# Analogica_HB_preto.net
KiCad netlist of a schematic drawn in EAGLE
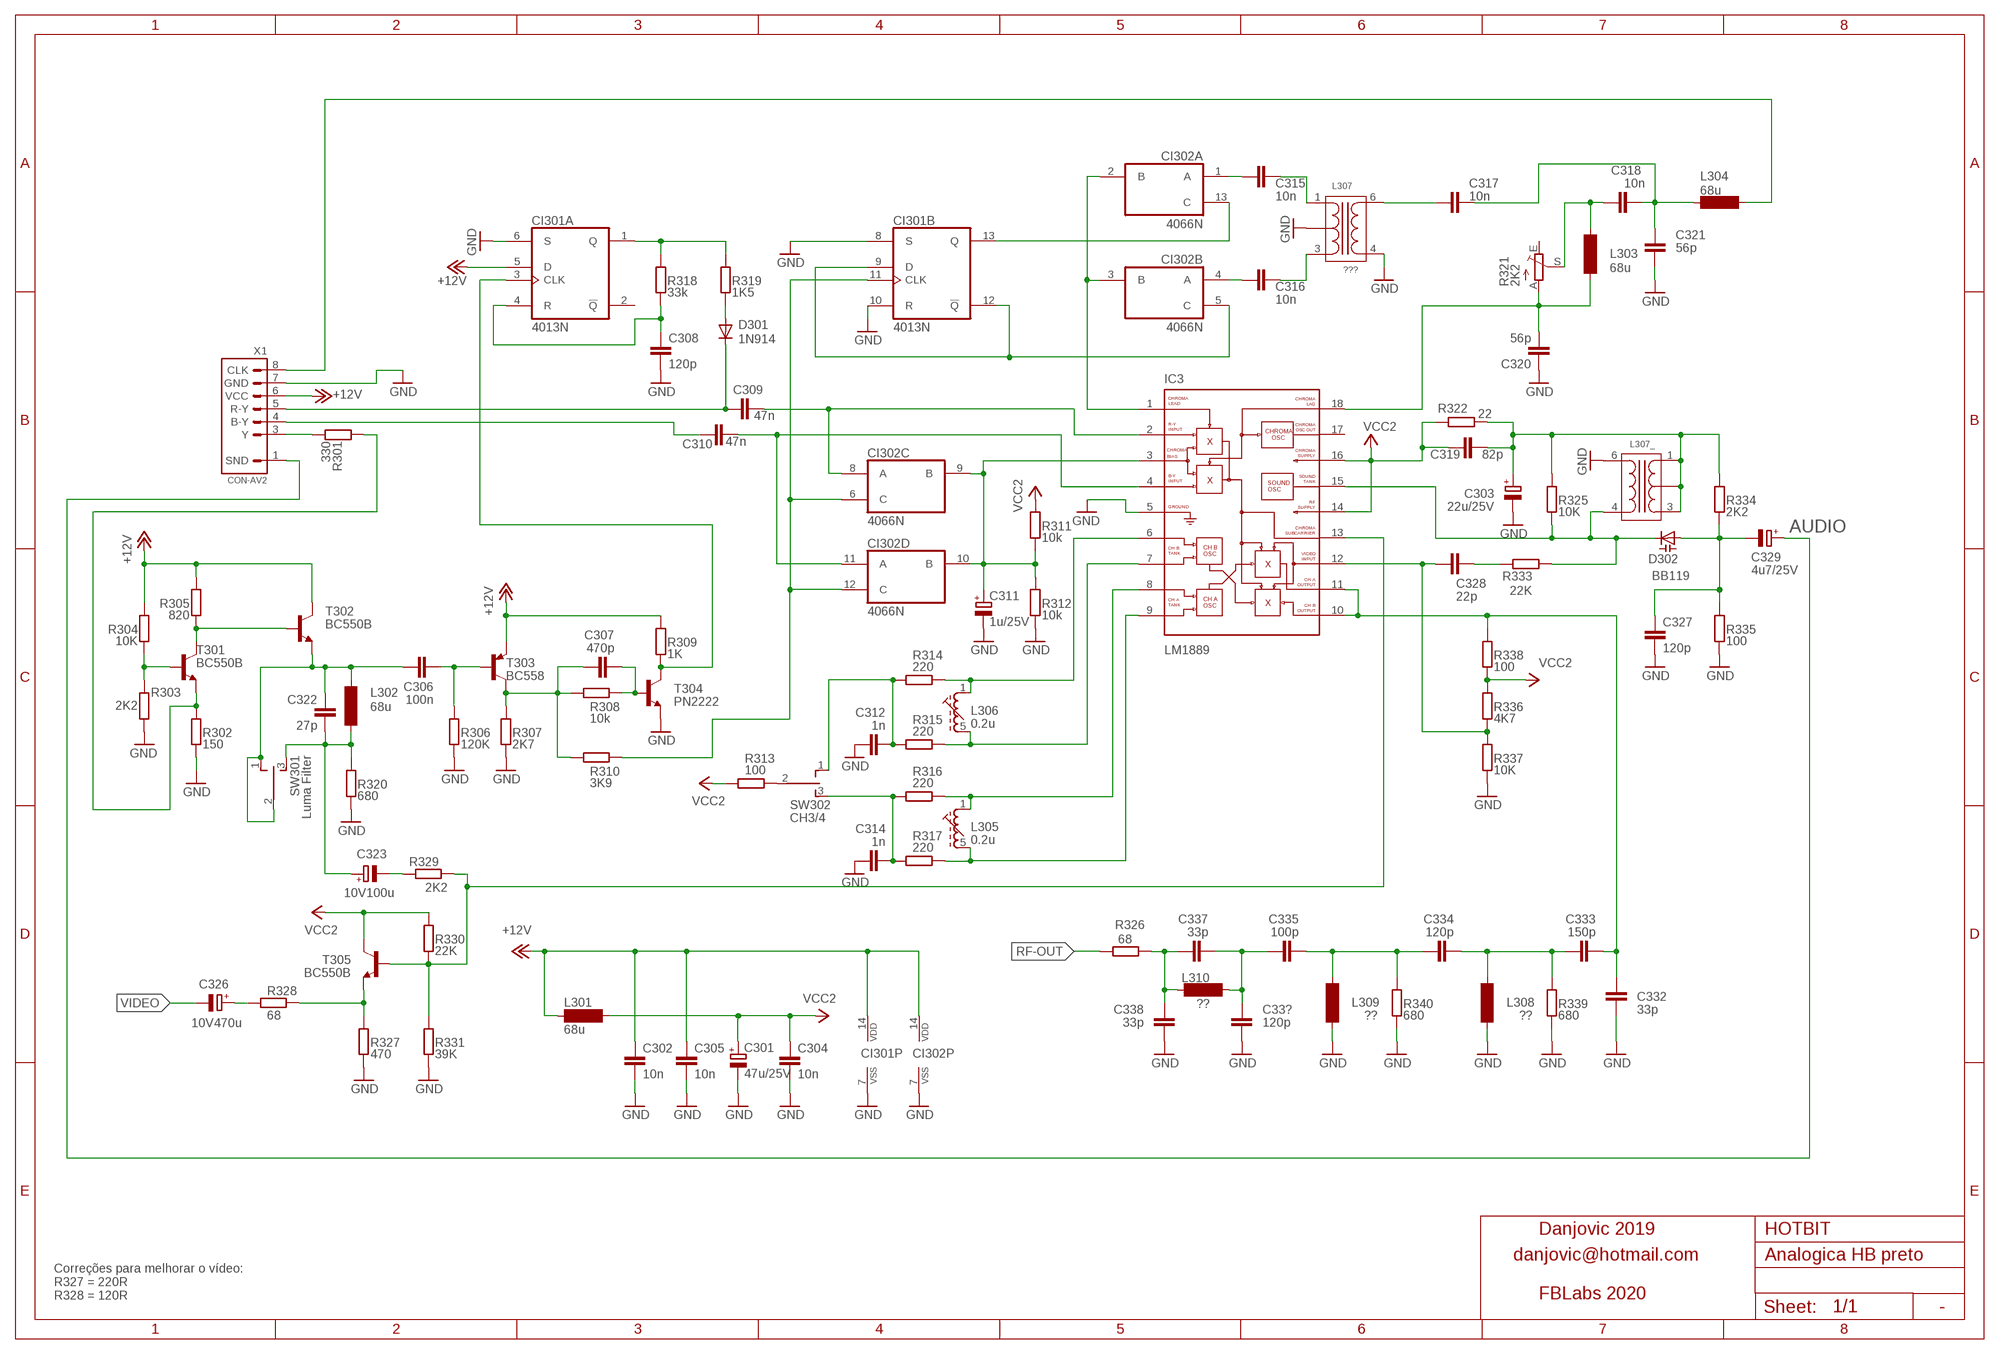
[diagram p0: schematic, sheet 1]

(export (version "E")
  (design (tool "Eeschema 10.0.6"))
  (components
    (comp (ref "C33?")
      (value "120p")
      (footprint "eagle-import:C050-024X044")
      (libsource (lib "eagle-import") (part "C-EU050-024X044"))
    )
    (comp (ref "C301")
      (value "47u/25V")
      (footprint "eagle-import:E2,5-5")
      (libsource (lib "eagle-import") (part "CPOL-EUE2.5-5"))
    )
    (comp (ref "C302")
      (value "10n")
      (footprint "eagle-import:C050-024X044")
      (libsource (lib "eagle-import") (part "C-EU050-024X044"))
    )
    (comp (ref "C303")
      (value "22u/25V")
      (footprint "eagle-import:E2,5-5")
      (libsource (lib "eagle-import") (part "CPOL-EUE2.5-5"))
    )
    (comp (ref "C304")
      (value "10n")
      (footprint "eagle-import:C050-024X044")
      (libsource (lib "eagle-import") (part "C-EU050-024X044"))
    )
    (comp (ref "C305")
      (value "10n")
      (footprint "eagle-import:C050-024X044")
      (libsource (lib "eagle-import") (part "C-EU050-024X044"))
    )
    (comp (ref "C306")
      (value "100n")
      (footprint "eagle-import:C050-024X044")
      (libsource (lib "eagle-import") (part "C-EU050-024X044"))
    )
    (comp (ref "C307")
      (value "470p")
      (footprint "eagle-import:C050-024X044")
      (libsource (lib "eagle-import") (part "C-EU050-024X044"))
    )
    (comp (ref "C308")
      (value "120p")
      (footprint "eagle-import:C050-024X044")
      (libsource (lib "eagle-import") (part "C-EU050-024X044"))
    )
    (comp (ref "C309")
      (value "47n")
      (footprint "eagle-import:C050-024X044")
      (libsource (lib "eagle-import") (part "C-EU050-024X044"))
    )
    (comp (ref "C310")
      (value "47n")
      (footprint "eagle-import:C050-024X044")
      (libsource (lib "eagle-import") (part "C-EU050-024X044"))
    )
    (comp (ref "C311")
      (value "1u/25V")
      (footprint "eagle-import:E2,5-5")
      (libsource (lib "eagle-import") (part "CPOL-EUE2.5-5"))
    )
    (comp (ref "C312")
      (value "1n")
      (footprint "eagle-import:C050-024X044")
      (libsource (lib "eagle-import") (part "C-EU050-024X044"))
    )
    (comp (ref "C314")
      (value "1n")
      (footprint "eagle-import:C050-024X044")
      (libsource (lib "eagle-import") (part "C-EU050-024X044"))
    )
    (comp (ref "C315")
      (value "10n")
      (footprint "eagle-import:C050-024X044")
      (libsource (lib "eagle-import") (part "C-EU050-024X044"))
    )
    (comp (ref "C316")
      (value "10n")
      (footprint "eagle-import:C050-024X044")
      (libsource (lib "eagle-import") (part "C-EU050-024X044"))
    )
    (comp (ref "C317")
      (value "10n")
      (footprint "eagle-import:C050-024X044")
      (libsource (lib "eagle-import") (part "C-EU050-024X044"))
    )
    (comp (ref "C318")
      (value "10n")
      (footprint "eagle-import:C050-024X044")
      (libsource (lib "eagle-import") (part "C-EU050-024X044"))
    )
    (comp (ref "C319")
      (value "82p")
      (footprint "eagle-import:C050-024X044")
      (libsource (lib "eagle-import") (part "C-EU050-024X044"))
    )
    (comp (ref "C320")
      (value "56p")
      (footprint "eagle-import:C050-024X044")
      (libsource (lib "eagle-import") (part "C-EU050-024X044"))
    )
    (comp (ref "C321")
      (value "56p")
      (footprint "eagle-import:C050-024X044")
      (libsource (lib "eagle-import") (part "C-EU050-024X044"))
    )
    (comp (ref "C322")
      (value "27p")
      (footprint "eagle-import:C050-024X044")
      (libsource (lib "eagle-import") (part "C-EU050-024X044"))
    )
    (comp (ref "C323")
      (value "10V100u")
      (footprint "eagle-import:E2,5-5")
      (libsource (lib "eagle-import") (part "CPOL-EUE2.5-5"))
    )
    (comp (ref "C326")
      (value "10V470u")
      (footprint "eagle-import:E2,5-5")
      (libsource (lib "eagle-import") (part "CPOL-EUE2.5-5"))
    )
    (comp (ref "C327")
      (value "120p")
      (footprint "eagle-import:C050-024X044")
      (libsource (lib "eagle-import") (part "C-EU050-024X044"))
    )
    (comp (ref "C328")
      (value "22p")
      (footprint "eagle-import:C050-024X044")
      (libsource (lib "eagle-import") (part "C-EU050-024X044"))
    )
    (comp (ref "C329")
      (value "4u7/25V")
      (footprint "eagle-import:E2,5-5")
      (libsource (lib "eagle-import") (part "CPOL-EUE2.5-5"))
    )
    (comp (ref "C332")
      (value "33p")
      (footprint "eagle-import:C050-024X044")
      (libsource (lib "eagle-import") (part "C-EU050-024X044"))
    )
    (comp (ref "C333")
      (value "150p")
      (footprint "eagle-import:C050-024X044")
      (libsource (lib "eagle-import") (part "C-EU050-024X044"))
    )
    (comp (ref "C334")
      (value "120p")
      (footprint "eagle-import:C050-024X044")
      (libsource (lib "eagle-import") (part "C-EU050-024X044"))
    )
    (comp (ref "C335")
      (value "100p")
      (footprint "eagle-import:C050-024X044")
      (libsource (lib "eagle-import") (part "C-EU050-024X044"))
    )
    (comp (ref "C337")
      (value "33p")
      (footprint "eagle-import:C050-024X044")
      (libsource (lib "eagle-import") (part "C-EU050-024X044"))
    )
    (comp (ref "C338")
      (value "33p")
      (footprint "eagle-import:C050-024X044")
      (libsource (lib "eagle-import") (part "C-EU050-024X044"))
    )
    (comp (ref "CI301")
      (value "4013N")
      (footprint "eagle-import:DIL14")
      (libsource (lib "eagle-import") (part "4013N"))
    )
    (comp (ref "CI302")
      (value "4066N")
      (footprint "eagle-import:DIL14")
      (libsource (lib "eagle-import") (part "4066N"))
    )
    (comp (ref "D301")
      (value "1N914")
      (footprint "eagle-import:DO35-7")
      (libsource (lib "eagle-import") (part "1N4148DO35-7"))
    )
    (comp (ref "D302")
      (value "BB119")
      (footprint "eagle-import:SOT54H")
      (libsource (lib "eagle-import") (part "BB112"))
    )
    (comp (ref "IC3")
      (value "LM1889")
      (footprint "eagle-import:DIL18")
      (libsource (lib "eagle-import") (part "LM1889"))
    )
    (comp (ref "L301")
      (value "68u")
      (footprint "eagle-import:SD75")
      (libsource (lib "eagle-import") (part "SD75"))
    )
    (comp (ref "L302")
      (value "68u")
      (footprint "eagle-import:SD75")
      (libsource (lib "eagle-import") (part "SD75"))
    )
    (comp (ref "L303")
      (value "68u")
      (footprint "eagle-import:SD75")
      (libsource (lib "eagle-import") (part "SD75"))
    )
    (comp (ref "L304")
      (value "68u")
      (footprint "eagle-import:SD75")
      (libsource (lib "eagle-import") (part "SD75"))
    )
    (comp (ref "L305")
      (value "0.2u")
      (footprint "eagle-import:71K")
      (libsource (lib "eagle-import") (part "51K"))
    )
    (comp (ref "L306")
      (value "0.2u")
      (footprint "eagle-import:71K")
      (libsource (lib "eagle-import") (part "51K"))
    )
    (comp (ref "L307")
      (value "???")
      (footprint "eagle-import:TRAFO-RF-6W")
      (libsource (lib "eagle-import") (part "TRAVO-RF-4W{dblquote}{dblquote}"))
    )
    (comp (ref "L307_")
      (value "TRAVO-RF-4W\"\"")
      (footprint "eagle-import:TRAFO-RF-6W")
      (libsource (lib "eagle-import") (part "TRAVO-RF-4W{dblquote}{dblquote}"))
    )
    (comp (ref "L308")
      (value "??")
      (footprint "eagle-import:SD75")
      (libsource (lib "eagle-import") (part "SD75"))
    )
    (comp (ref "L309")
      (value "??")
      (footprint "eagle-import:SD75")
      (libsource (lib "eagle-import") (part "SD75"))
    )
    (comp (ref "L310")
      (value "??")
      (footprint "eagle-import:SD75")
      (libsource (lib "eagle-import") (part "SD75"))
    )
    (comp (ref "R301")
      (value "330")
      (footprint "eagle-import:0204_7")
      (libsource (lib "eagle-import") (part "R-EU_0204/7"))
    )
    (comp (ref "R302")
      (value "150")
      (footprint "eagle-import:0204_7")
      (libsource (lib "eagle-import") (part "R-EU_0204/7"))
    )
    (comp (ref "R303")
      (value "2K2")
      (footprint "eagle-import:0204_7")
      (libsource (lib "eagle-import") (part "R-EU_0204/7"))
    )
    (comp (ref "R304")
      (value "10K")
      (footprint "eagle-import:0204_7")
      (libsource (lib "eagle-import") (part "R-EU_0204/7"))
    )
    (comp (ref "R305")
      (value "820")
      (footprint "eagle-import:0204_7")
      (libsource (lib "eagle-import") (part "R-EU_0204/7"))
    )
    (comp (ref "R306")
      (value "120K")
      (footprint "eagle-import:0204_7")
      (libsource (lib "eagle-import") (part "R-EU_0204/7"))
    )
    (comp (ref "R307")
      (value "2K7")
      (footprint "eagle-import:0204_7")
      (libsource (lib "eagle-import") (part "R-EU_0204/7"))
    )
    (comp (ref "R308")
      (value "10k")
      (footprint "eagle-import:0204_7")
      (libsource (lib "eagle-import") (part "R-EU_0204/7"))
    )
    (comp (ref "R309")
      (value "1K")
      (footprint "eagle-import:0204_7")
      (libsource (lib "eagle-import") (part "R-EU_0204/7"))
    )
    (comp (ref "R310")
      (value "3K9")
      (footprint "eagle-import:0204_7")
      (libsource (lib "eagle-import") (part "R-EU_0204/7"))
    )
    (comp (ref "R311")
      (value "10k")
      (footprint "eagle-import:0204_7")
      (libsource (lib "eagle-import") (part "R-EU_0204/7"))
    )
    (comp (ref "R312")
      (value "10k")
      (footprint "eagle-import:0204_7")
      (libsource (lib "eagle-import") (part "R-EU_0204/7"))
    )
    (comp (ref "R313")
      (value "100")
      (footprint "eagle-import:0204_7")
      (libsource (lib "eagle-import") (part "R-EU_0204/7"))
    )
    (comp (ref "R314")
      (value "220")
      (footprint "eagle-import:0204_7")
      (libsource (lib "eagle-import") (part "R-EU_0204/7"))
    )
    (comp (ref "R315")
      (value "220")
      (footprint "eagle-import:0204_7")
      (libsource (lib "eagle-import") (part "R-EU_0204/7"))
    )
    (comp (ref "R316")
      (value "220")
      (footprint "eagle-import:0204_7")
      (libsource (lib "eagle-import") (part "R-EU_0204/7"))
    )
    (comp (ref "R317")
      (value "220")
      (footprint "eagle-import:0204_7")
      (libsource (lib "eagle-import") (part "R-EU_0204/7"))
    )
    (comp (ref "R318")
      (value "33k")
      (footprint "eagle-import:0204_7")
      (libsource (lib "eagle-import") (part "R-EU_0204/7"))
    )
    (comp (ref "R319")
      (value "1K5")
      (footprint "eagle-import:0204_7")
      (libsource (lib "eagle-import") (part "R-EU_0204/7"))
    )
    (comp (ref "R320")
      (value "680")
      (footprint "eagle-import:0204_7")
      (libsource (lib "eagle-import") (part "R-EU_0204/7"))
    )
    (comp (ref "R321")
      (value "2K2")
      (footprint "eagle-import:S64Y")
      (libsource (lib "eagle-import") (part "TRIM_EU-S64Y"))
    )
    (comp (ref "R322")
      (value "22")
      (footprint "eagle-import:0204_7")
      (libsource (lib "eagle-import") (part "R-EU_0204/7"))
    )
    (comp (ref "R325")
      (value "10K")
      (footprint "eagle-import:0204_7")
      (libsource (lib "eagle-import") (part "R-EU_0204/7"))
    )
    (comp (ref "R326")
      (value "68")
      (footprint "eagle-import:0204_7")
      (libsource (lib "eagle-import") (part "R-EU_0204/7"))
    )
    (comp (ref "R327")
      (value "470")
      (footprint "eagle-import:0204_7")
      (libsource (lib "eagle-import") (part "R-EU_0204/7"))
    )
    (comp (ref "R328")
      (value "68")
      (footprint "eagle-import:0204_7")
      (libsource (lib "eagle-import") (part "R-EU_0204/7"))
    )
    (comp (ref "R329")
      (value "2K2")
      (footprint "eagle-import:0204_7")
      (libsource (lib "eagle-import") (part "R-EU_0204/7"))
    )
    (comp (ref "R330")
      (value "22K")
      (footprint "eagle-import:0204_7")
      (libsource (lib "eagle-import") (part "R-EU_0204/7"))
    )
    (comp (ref "R331")
      (value "39K")
      (footprint "eagle-import:0204_7")
      (libsource (lib "eagle-import") (part "R-EU_0204/7"))
    )
    (comp (ref "R333")
      (value "22K")
      (footprint "eagle-import:0204_7")
      (libsource (lib "eagle-import") (part "R-EU_0204/7"))
    )
    (comp (ref "R334")
      (value "2K2")
      (footprint "eagle-import:0204_7")
      (libsource (lib "eagle-import") (part "R-EU_0204/7"))
    )
    (comp (ref "R335")
      (value "100")
      (footprint "eagle-import:0204_7")
      (libsource (lib "eagle-import") (part "R-EU_0204/7"))
    )
    (comp (ref "R336")
      (value "4K7")
      (footprint "eagle-import:0204_7")
      (libsource (lib "eagle-import") (part "R-EU_0204/7"))
    )
    (comp (ref "R337")
      (value "10K")
      (footprint "eagle-import:0204_7")
      (libsource (lib "eagle-import") (part "R-EU_0204/7"))
    )
    (comp (ref "R338")
      (value "100")
      (footprint "eagle-import:0204_7")
      (libsource (lib "eagle-import") (part "R-EU_0204/7"))
    )
    (comp (ref "R339")
      (value "680")
      (footprint "eagle-import:0204_7")
      (libsource (lib "eagle-import") (part "R-EU_0204/7"))
    )
    (comp (ref "R340")
      (value "680")
      (footprint "eagle-import:0204_7")
      (libsource (lib "eagle-import") (part "R-EU_0204/7"))
    )
    (comp (ref "SW301")
      (value "Luma Filter")
      (footprint "eagle-import:TL3XPO")
      (libsource (lib "eagle-import") (part "TL39PO"))
    )
    (comp (ref "SW302")
      (value "CH3/4")
      (footprint "eagle-import:TL3XPO")
      (libsource (lib "eagle-import") (part "TL39PO"))
    )
    (comp (ref "T301")
      (value "BC550B")
      (footprint "eagle-import:TO92-EBC")
      (libsource (lib "eagle-import") (part "-NPN-TO92-EBCBC317"))
    )
    (comp (ref "T302")
      (value "BC550B")
      (footprint "eagle-import:TO92-EBC")
      (libsource (lib "eagle-import") (part "-NPN-TO92-EBCBC317"))
    )
    (comp (ref "T303")
      (value "BC558")
      (footprint "eagle-import:TO92-EBC")
      (libsource (lib "eagle-import") (part "BC327"))
    )
    (comp (ref "T304")
      (value "PN2222")
      (footprint "eagle-import:TO92-CBE")
      (libsource (lib "eagle-import") (part "-NPN-TO92-CBEMPS2222A"))
    )
    (comp (ref "T305")
      (value "BC550B")
      (footprint "eagle-import:TO92-EBC")
      (libsource (lib "eagle-import") (part "BC550B"))
    )
    (comp (ref "X1")
      (value "CON-AV2")
      (footprint "eagle-import:CON-AV2")
      (libsource (lib "eagle-import") (part "CON-AV2"))
    )
  )
  (nets
    (net (code "1") (name "+12V") (class "Default")
      (node (ref "C302") (pin "1") (pinfunction "1_1") (pintype "passive"))
      (node (ref "C305") (pin "1") (pinfunction "1_1") (pintype "passive"))
      (node (ref "CI301") (pin "14") (pinfunction "VDD_14") (pintype "power_in"))
      (node (ref "CI301") (pin "5") (pinfunction "D_5") (pintype "input"))
      (node (ref "CI302") (pin "14") (pinfunction "VDD_14") (pintype "power_in"))
      (node (ref "L301") (pin "1") (pinfunction "1_1") (pintype "passive"))
      (node (ref "R304") (pin "2") (pinfunction "2_2") (pintype "passive"))
      (node (ref "R305") (pin "2") (pinfunction "2_2") (pintype "passive"))
      (node (ref "R309") (pin "2") (pinfunction "2_2") (pintype "passive"))
      (node (ref "T302") (pin "C") (pinfunction "C_C") (pintype "passive"))
      (node (ref "T303") (pin "E") (pinfunction "E_E") (pintype "passive"))
      (node (ref "X1") (pin "6") (pinfunction "VCC_6") (pintype "power_in"))
    )
    (net (code "2") (name "/AUDIO") (class "Default")
      (node (ref "C329") (pin "+") (pinfunction "+_+") (pintype "passive"))
      (node (ref "X1") (pin "1") (pinfunction "SND_1") (pintype "input"))
    )
    (net (code "3") (name "GND") (class "Default")
      (node (ref "C301") (pin "-") (pinfunction "-_-") (pintype "passive"))
      (node (ref "C302") (pin "2") (pinfunction "2_2") (pintype "passive"))
      (node (ref "C303") (pin "-") (pinfunction "-_-") (pintype "passive"))
      (node (ref "C304") (pin "2") (pinfunction "2_2") (pintype "passive"))
      (node (ref "C305") (pin "2") (pinfunction "2_2") (pintype "passive"))
      (node (ref "C308") (pin "2") (pinfunction "2_2") (pintype "passive"))
      (node (ref "C311") (pin "-") (pinfunction "-_-") (pintype "passive"))
      (node (ref "C312") (pin "2") (pinfunction "2_2") (pintype "passive"))
      (node (ref "C314") (pin "2") (pinfunction "2_2") (pintype "passive"))
      (node (ref "C320") (pin "1") (pinfunction "1_1") (pintype "passive"))
      (node (ref "C321") (pin "2") (pinfunction "2_2") (pintype "passive"))
      (node (ref "C327") (pin "2") (pinfunction "2_2") (pintype "passive"))
      (node (ref "C332") (pin "2") (pinfunction "2_2") (pintype "passive"))
      (node (ref "C338") (pin "2") (pinfunction "2_2") (pintype "passive"))
      (node (ref "C33?") (pin "2") (pinfunction "2_2") (pintype "passive"))
      (node (ref "CI301") (pin "10") (pinfunction "R_10") (pintype "input"))
      (node (ref "CI301") (pin "6") (pinfunction "S_6") (pintype "input"))
      (node (ref "CI301") (pin "7") (pinfunction "VSS_7") (pintype "power_in"))
      (node (ref "CI301") (pin "8") (pinfunction "S_8") (pintype "input"))
      (node (ref "CI302") (pin "7") (pinfunction "VSS_7") (pintype "power_in"))
      (node (ref "IC3") (pin "5") (pinfunction "P$5_5") (pintype "power_in"))
      (node (ref "L307") (pin "2") (pinfunction "2_2") (pintype "passive"))
      (node (ref "L307") (pin "4") (pinfunction "4_4") (pintype "bidirectional"))
      (node (ref "L307_") (pin "6") (pinfunction "6_6") (pintype "bidirectional"))
      (node (ref "L308") (pin "1") (pinfunction "1_1") (pintype "passive"))
      (node (ref "L309") (pin "1") (pinfunction "1_1") (pintype "passive"))
      (node (ref "R302") (pin "1") (pinfunction "1_1") (pintype "passive"))
      (node (ref "R303") (pin "1") (pinfunction "1_1") (pintype "passive"))
      (node (ref "R306") (pin "1") (pinfunction "1_1") (pintype "passive"))
      (node (ref "R307") (pin "1") (pinfunction "1_1") (pintype "passive"))
      (node (ref "R312") (pin "1") (pinfunction "1_1") (pintype "passive"))
      (node (ref "R320") (pin "1") (pinfunction "1_1") (pintype "passive"))
      (node (ref "R327") (pin "1") (pinfunction "1_1") (pintype "passive"))
      (node (ref "R331") (pin "1") (pinfunction "1_1") (pintype "passive"))
      (node (ref "R335") (pin "1") (pinfunction "1_1") (pintype "passive"))
      (node (ref "R337") (pin "1") (pinfunction "1_1") (pintype "passive"))
      (node (ref "R339") (pin "1") (pinfunction "1_1") (pintype "passive"))
      (node (ref "R340") (pin "1") (pinfunction "1_1") (pintype "passive"))
      (node (ref "T304") (pin "E") (pinfunction "E_E") (pintype "passive"))
      (node (ref "X1") (pin "7") (pinfunction "GND_7") (pintype "power_in"))
    )
    (net (code "4") (name "Net-(C303-Pad+)") (class "Default")
      (node (ref "C303") (pin "+") (pinfunction "+_+") (pintype "passive"))
      (node (ref "C319") (pin "2") (pinfunction "2_2") (pintype "passive"))
      (node (ref "L307_") (pin "1") (pinfunction "1_1") (pintype "bidirectional"))
      (node (ref "L307_") (pin "2") (pinfunction "2_2") (pintype "passive"))
      (node (ref "L307_") (pin "3") (pinfunction "3_3") (pintype "bidirectional"))
      (node (ref "R322") (pin "1") (pinfunction "1_1") (pintype "passive"))
      (node (ref "R325") (pin "2") (pinfunction "2_2") (pintype "passive"))
      (node (ref "R334") (pin "2") (pinfunction "2_2") (pintype "passive"))
    )
    (net (code "5") (name "Net-(C306-Pad1)") (class "Default")
      (node (ref "C306") (pin "1") (pinfunction "1_1") (pintype "passive"))
      (node (ref "R306") (pin "2") (pinfunction "2_2") (pintype "passive"))
      (node (ref "T303") (pin "B") (pinfunction "B_B") (pintype "passive"))
    )
    (net (code "6") (name "Net-(C307-Pad1)") (class "Default")
      (node (ref "C307") (pin "1") (pinfunction "1_1") (pintype "passive"))
      (node (ref "R308") (pin "2") (pinfunction "2_2") (pintype "passive"))
      (node (ref "T304") (pin "B") (pinfunction "B_B") (pintype "passive"))
    )
    (net (code "7") (name "Net-(C307-Pad2)") (class "Default")
      (node (ref "C307") (pin "2") (pinfunction "2_2") (pintype "passive"))
      (node (ref "R307") (pin "2") (pinfunction "2_2") (pintype "passive"))
      (node (ref "R308") (pin "1") (pinfunction "1_1") (pintype "passive"))
      (node (ref "R310") (pin "1") (pinfunction "1_1") (pintype "passive"))
      (node (ref "T303") (pin "C") (pinfunction "C_C") (pintype "passive"))
    )
    (net (code "8") (name "Net-(C315-Pad2)") (class "Default")
      (node (ref "C315") (pin "2") (pinfunction "2_2") (pintype "passive"))
      (node (ref "L307") (pin "1") (pinfunction "1_1") (pintype "bidirectional"))
    )
    (net (code "9") (name "Net-(C316-Pad2)") (class "Default")
      (node (ref "C316") (pin "2") (pinfunction "2_2") (pintype "passive"))
      (node (ref "L307") (pin "3") (pinfunction "3_3") (pintype "bidirectional"))
    )
    (net (code "10") (name "Net-(C317-Pad1)") (class "Default")
      (node (ref "C317") (pin "1") (pinfunction "1_1") (pintype "passive"))
      (node (ref "L307") (pin "6") (pinfunction "6_6") (pintype "bidirectional"))
    )
    (net (code "11") (name "Net-(C317-Pad2)") (class "Default")
      (node (ref "C317") (pin "2") (pinfunction "2_2") (pintype "passive"))
      (node (ref "C318") (pin "2") (pinfunction "2_2") (pintype "passive"))
      (node (ref "C321") (pin "1") (pinfunction "1_1") (pintype "passive"))
      (node (ref "L304") (pin "1") (pinfunction "1_1") (pintype "passive"))
    )
    (net (code "12") (name "Net-(C318-Pad1)") (class "Default")
      (node (ref "C318") (pin "1") (pinfunction "1_1") (pintype "passive"))
      (node (ref "L303") (pin "2") (pinfunction "2_2") (pintype "passive"))
      (node (ref "R321") (pin "S") (pinfunction "S_S") (pintype "passive"))
    )
    (net (code "13") (name "Net-(C323-Pad-)") (class "Default")
      (node (ref "C323") (pin "-") (pinfunction "-_-") (pintype "passive"))
      (node (ref "R329") (pin "2") (pinfunction "2_2") (pintype "passive"))
    )
    (net (code "14") (name "Net-(C326-Pad+)") (class "Default")
      (node (ref "C326") (pin "+") (pinfunction "+_+") (pintype "passive"))
      (node (ref "R328") (pin "1") (pinfunction "1_1") (pintype "passive"))
    )
    (net (code "15") (name "Net-(C327-Pad1)") (class "Default")
      (node (ref "C327") (pin "1") (pinfunction "1_1") (pintype "passive"))
      (node (ref "C329") (pin "-") (pinfunction "-_-") (pintype "passive"))
      (node (ref "D302") (pin "A") (pinfunction "A_A") (pintype "passive"))
      (node (ref "R334") (pin "1") (pinfunction "1_1") (pintype "passive"))
      (node (ref "R335") (pin "2") (pinfunction "2_2") (pintype "passive"))
    )
    (net (code "16") (name "Net-(C328-Pad2)") (class "Default")
      (node (ref "C328") (pin "2") (pinfunction "2_2") (pintype "passive"))
      (node (ref "R333") (pin "2") (pinfunction "2_2") (pintype "passive"))
    )
    (net (code "17") (name "Net-(C333-Pad2)") (class "Default")
      (node (ref "C333") (pin "2") (pinfunction "2_2") (pintype "passive"))
      (node (ref "C334") (pin "1") (pinfunction "1_1") (pintype "passive"))
      (node (ref "L308") (pin "2") (pinfunction "2_2") (pintype "passive"))
      (node (ref "R339") (pin "2") (pinfunction "2_2") (pintype "passive"))
    )
    (net (code "18") (name "Net-(C334-Pad2)") (class "Default")
      (node (ref "C334") (pin "2") (pinfunction "2_2") (pintype "passive"))
      (node (ref "C335") (pin "1") (pinfunction "1_1") (pintype "passive"))
      (node (ref "L309") (pin "2") (pinfunction "2_2") (pintype "passive"))
      (node (ref "R340") (pin "2") (pinfunction "2_2") (pintype "passive"))
    )
    (net (code "19") (name "Net-(C335-Pad2)") (class "Default")
      (node (ref "C335") (pin "2") (pinfunction "2_2") (pintype "passive"))
      (node (ref "C337") (pin "1") (pinfunction "1_1") (pintype "passive"))
      (node (ref "C33?") (pin "1") (pinfunction "1_1") (pintype "passive"))
      (node (ref "L310") (pin "1") (pinfunction "1_1") (pintype "passive"))
    )
    (net (code "20") (name "Net-(C337-Pad2)") (class "Default")
      (node (ref "C337") (pin "2") (pinfunction "2_2") (pintype "passive"))
      (node (ref "C338") (pin "1") (pinfunction "1_1") (pintype "passive"))
      (node (ref "L310") (pin "2") (pinfunction "2_2") (pintype "passive"))
      (node (ref "R326") (pin "1") (pinfunction "1_1") (pintype "passive"))
    )
    (net (code "21") (name "Net-(CI301A-CLK)") (class "Default")
      (node (ref "CI301") (pin "3") (pinfunction "CLK_3") (pintype "input"))
      (node (ref "R309") (pin "1") (pinfunction "1_1") (pintype "passive"))
      (node (ref "T304") (pin "C") (pinfunction "C_C") (pintype "passive"))
    )
    (net (code "22") (name "Net-(CI301A-Q)") (class "Default")
      (node (ref "CI301") (pin "1") (pinfunction "Q_1") (pintype "output"))
      (node (ref "R318") (pin "2") (pinfunction "2_2") (pintype "passive"))
      (node (ref "R319") (pin "2") (pinfunction "2_2") (pintype "passive"))
    )
    (net (code "23") (name "Net-(CI301A-R)") (class "Default")
      (node (ref "C308") (pin "1") (pinfunction "1_1") (pintype "passive"))
      (node (ref "CI301") (pin "4") (pinfunction "R_4") (pintype "input"))
      (node (ref "R318") (pin "1") (pinfunction "1_1") (pintype "passive"))
    )
    (net (code "24") (name "Net-(CI301B-CLK)") (class "Default")
      (node (ref "CI301") (pin "11") (pinfunction "CLK_11") (pintype "input"))
      (node (ref "CI302") (pin "12") (pinfunction "C_12") (pintype "input"))
      (node (ref "CI302") (pin "6") (pinfunction "C_6") (pintype "input"))
      (node (ref "R310") (pin "2") (pinfunction "2_2") (pintype "passive"))
    )
    (net (code "25") (name "Net-(CI301B-D)") (class "Default")
      (node (ref "CI301") (pin "12") (pinfunction "~{Q}_12") (pintype "output"))
      (node (ref "CI301") (pin "9") (pinfunction "D_9") (pintype "input"))
      (node (ref "CI302") (pin "5") (pinfunction "C_5") (pintype "input"))
    )
    (net (code "26") (name "Net-(CI301B-Q)") (class "Default")
      (node (ref "CI301") (pin "13") (pinfunction "Q_13") (pintype "output"))
      (node (ref "CI302") (pin "13") (pinfunction "C_13") (pintype "input"))
    )
    (net (code "27") (name "Net-(CI302A-A)") (class "Default")
      (node (ref "C315") (pin "1") (pinfunction "1_1") (pintype "passive"))
      (node (ref "CI302") (pin "1") (pinfunction "A_1") (pintype "tri_state"))
    )
    (net (code "28") (name "Net-(CI302A-B)") (class "Default")
      (node (ref "CI302") (pin "2") (pinfunction "B_2") (pintype "tri_state"))
      (node (ref "CI302") (pin "3") (pinfunction "B_3") (pintype "tri_state"))
      (node (ref "IC3") (pin "1") (pinfunction "P$1_1") (pintype "input"))
    )
    (net (code "29") (name "Net-(CI302B-A)") (class "Default")
      (node (ref "C316") (pin "1") (pinfunction "1_1") (pintype "passive"))
      (node (ref "CI302") (pin "4") (pinfunction "A_4") (pintype "tri_state"))
    )
    (net (code "30") (name "Net-(CI302C-A)") (class "Default")
      (node (ref "C309") (pin "2") (pinfunction "2_2") (pintype "passive"))
      (node (ref "CI302") (pin "8") (pinfunction "A_8") (pintype "tri_state"))
      (node (ref "IC3") (pin "2") (pinfunction "P$2_2") (pintype "input"))
    )
    (net (code "31") (name "Net-(CI302C-B)") (class "Default")
      (node (ref "C311") (pin "+") (pinfunction "+_+") (pintype "passive"))
      (node (ref "CI302") (pin "10") (pinfunction "B_10") (pintype "tri_state"))
      (node (ref "CI302") (pin "9") (pinfunction "B_9") (pintype "tri_state"))
      (node (ref "IC3") (pin "3") (pinfunction "P$3_3") (pintype "input"))
      (node (ref "R311") (pin "1") (pinfunction "1_1") (pintype "passive"))
      (node (ref "R312") (pin "2") (pinfunction "2_2") (pintype "passive"))
    )
    (net (code "32") (name "Net-(CI302D-A)") (class "Default")
      (node (ref "C310") (pin "2") (pinfunction "2_2") (pintype "passive"))
      (node (ref "CI302") (pin "11") (pinfunction "A_11") (pintype "tri_state"))
      (node (ref "IC3") (pin "4") (pinfunction "P$4_4") (pintype "input"))
    )
    (net (code "33") (name "Net-(D301-PadA)") (class "Default")
      (node (ref "D301") (pin "A") (pinfunction "A_A") (pintype "passive"))
      (node (ref "R319") (pin "1") (pinfunction "1_1") (pintype "passive"))
    )
    (net (code "34") (name "Net-(IC3-P$6)") (class "Default")
      (node (ref "IC3") (pin "6") (pinfunction "P$6_6") (pintype "bidirectional"))
      (node (ref "L306") (pin "1") (pinfunction "A_1") (pintype "passive"))
      (node (ref "R314") (pin "2") (pinfunction "2_2") (pintype "passive"))
    )
    (net (code "35") (name "Net-(IC3-P$7)") (class "Default")
      (node (ref "IC3") (pin "7") (pinfunction "P$7_7") (pintype "bidirectional"))
      (node (ref "L306") (pin "5") (pinfunction "E_5") (pintype "passive"))
      (node (ref "R315") (pin "2") (pinfunction "2_2") (pintype "passive"))
    )
    (net (code "36") (name "Net-(IC3-P$8)") (class "Default")
      (node (ref "IC3") (pin "8") (pinfunction "P$8_8") (pintype "bidirectional"))
      (node (ref "L305") (pin "1") (pinfunction "A_1") (pintype "passive"))
      (node (ref "R316") (pin "2") (pinfunction "2_2") (pintype "passive"))
    )
    (net (code "37") (name "Net-(IC3-P$9)") (class "Default")
      (node (ref "IC3") (pin "9") (pinfunction "P$9_9") (pintype "bidirectional"))
      (node (ref "L305") (pin "5") (pinfunction "E_5") (pintype "passive"))
      (node (ref "R317") (pin "2") (pinfunction "2_2") (pintype "passive"))
    )
    (net (code "38") (name "Net-(IC3-P$10)") (class "Default")
      (node (ref "C332") (pin "1") (pinfunction "1_1") (pintype "passive"))
      (node (ref "C333") (pin "1") (pinfunction "1_1") (pintype "passive"))
      (node (ref "IC3") (pin "10") (pinfunction "P$10_10") (pintype "output"))
      (node (ref "IC3") (pin "11") (pinfunction "P$11_11") (pintype "output"))
      (node (ref "R338") (pin "2") (pinfunction "2_2") (pintype "passive"))
    )
    (net (code "39") (name "Net-(IC3-P$12)") (class "Default")
      (node (ref "C328") (pin "1") (pinfunction "1_1") (pintype "passive"))
      (node (ref "IC3") (pin "12") (pinfunction "P$12_12") (pintype "input"))
      (node (ref "R336") (pin "1") (pinfunction "1_1") (pintype "passive"))
      (node (ref "R337") (pin "2") (pinfunction "2_2") (pintype "passive"))
    )
    (net (code "40") (name "Net-(IC3-P$13)") (class "Default")
      (node (ref "IC3") (pin "13") (pinfunction "P$13_13") (pintype "output"))
      (node (ref "R329") (pin "1") (pinfunction "1_1") (pintype "passive"))
      (node (ref "R330") (pin "1") (pinfunction "1_1") (pintype "passive"))
      (node (ref "R331") (pin "2") (pinfunction "2_2") (pintype "passive"))
      (node (ref "T305") (pin "B") (pinfunction "B_B") (pintype "passive"))
    )
    (net (code "41") (name "Net-(IC3-P$15)") (class "Default")
      (node (ref "D302") (pin "C") (pinfunction "C_C") (pintype "passive"))
      (node (ref "IC3") (pin "15") (pinfunction "P$15_15") (pintype "bidirectional"))
      (node (ref "L307_") (pin "4") (pinfunction "4_4") (pintype "bidirectional"))
      (node (ref "R325") (pin "1") (pinfunction "1_1") (pintype "passive"))
      (node (ref "R333") (pin "1") (pinfunction "1_1") (pintype "passive"))
    )
    (net (code "42") (name "Net-(IC3-P$18)") (class "Default")
      (node (ref "C320") (pin "2") (pinfunction "2_2") (pintype "passive"))
      (node (ref "IC3") (pin "18") (pinfunction "P$18_18") (pintype "bidirectional"))
      (node (ref "L303") (pin "1") (pinfunction "1_1") (pintype "passive"))
      (node (ref "R321") (pin "A") (pinfunction "A_A") (pintype "passive"))
    )
    (net (code "43") (name "Net-(R301-Pad2)") (class "Default")
      (node (ref "R301") (pin "2") (pinfunction "2_2") (pintype "passive"))
      (node (ref "R302") (pin "2") (pinfunction "2_2") (pintype "passive"))
      (node (ref "T301") (pin "E") (pinfunction "E_E") (pintype "passive"))
    )
    (net (code "44") (name "Net-(R303-Pad2)") (class "Default")
      (node (ref "R303") (pin "2") (pinfunction "2_2") (pintype "passive"))
      (node (ref "R304") (pin "1") (pinfunction "1_1") (pintype "passive"))
      (node (ref "T301") (pin "B") (pinfunction "B_B") (pintype "passive"))
    )
    (net (code "45") (name "Net-(R305-Pad1)") (class "Default")
      (node (ref "R305") (pin "1") (pinfunction "1_1") (pintype "passive"))
      (node (ref "T301") (pin "C") (pinfunction "C_C") (pintype "passive"))
      (node (ref "T302") (pin "B") (pinfunction "B_B") (pintype "passive"))
    )
    (net (code "46") (name "Net-(R327-Pad2)") (class "Default")
      (node (ref "R327") (pin "2") (pinfunction "2_2") (pintype "passive"))
      (node (ref "R328") (pin "2") (pinfunction "2_2") (pintype "passive"))
      (node (ref "T305") (pin "E") (pinfunction "E_E") (pintype "passive"))
    )
    (net (code "47") (name "Net-(SW301-O)") (class "Default")
      (node (ref "C306") (pin "2") (pinfunction "2_2") (pintype "passive"))
      (node (ref "C322") (pin "1") (pinfunction "1_1") (pintype "passive"))
      (node (ref "L302") (pin "2") (pinfunction "2_2") (pintype "passive"))
      (node (ref "SW301") (pin "1") (pinfunction "O_1") (pintype "passive"))
      (node (ref "SW301") (pin "2") (pinfunction "P_2") (pintype "passive"))
      (node (ref "T302") (pin "E") (pinfunction "E_E") (pintype "passive"))
    )
    (net (code "48") (name "Net-(SW301-S)") (class "Default")
      (node (ref "C322") (pin "2") (pinfunction "2_2") (pintype "passive"))
      (node (ref "C323") (pin "+") (pinfunction "+_+") (pintype "passive"))
      (node (ref "L302") (pin "1") (pinfunction "1_1") (pintype "passive"))
      (node (ref "R320") (pin "2") (pinfunction "2_2") (pintype "passive"))
      (node (ref "SW301") (pin "3") (pinfunction "S_3") (pintype "passive"))
    )
    (net (code "49") (name "Net-(SW302-O)") (class "Default")
      (node (ref "C312") (pin "1") (pinfunction "1_1") (pintype "passive"))
      (node (ref "R314") (pin "1") (pinfunction "1_1") (pintype "passive"))
      (node (ref "R315") (pin "1") (pinfunction "1_1") (pintype "passive"))
      (node (ref "SW302") (pin "1") (pinfunction "O_1") (pintype "passive"))
    )
    (net (code "50") (name "Net-(SW302-P)") (class "Default")
      (node (ref "R313") (pin "2") (pinfunction "2_2") (pintype "passive"))
      (node (ref "SW302") (pin "2") (pinfunction "P_2") (pintype "passive"))
    )
    (net (code "51") (name "Net-(SW302-S)") (class "Default")
      (node (ref "C314") (pin "1") (pinfunction "1_1") (pintype "passive"))
      (node (ref "R316") (pin "1") (pinfunction "1_1") (pintype "passive"))
      (node (ref "R317") (pin "1") (pinfunction "1_1") (pintype "passive"))
      (node (ref "SW302") (pin "3") (pinfunction "S_3") (pintype "passive"))
    )
    (net (code "52") (name "Net-(X1-B-Y)") (class "Default")
      (node (ref "C310") (pin "1") (pinfunction "1_1") (pintype "passive"))
      (node (ref "X1") (pin "4") (pinfunction "B-Y_4") (pintype "input"))
    )
    (net (code "53") (name "Net-(X1-CLK)") (class "Default")
      (node (ref "L304") (pin "2") (pinfunction "2_2") (pintype "passive"))
      (node (ref "X1") (pin "8") (pinfunction "CLK_8") (pintype "input"))
    )
    (net (code "54") (name "Net-(X1-R-Y)") (class "Default")
      (node (ref "C309") (pin "1") (pinfunction "1_1") (pintype "passive"))
      (node (ref "D301") (pin "C") (pinfunction "C_C") (pintype "passive"))
      (node (ref "X1") (pin "5") (pinfunction "R-Y_5") (pintype "input"))
    )
    (net (code "55") (name "Net-(X1-Y)") (class "Default")
      (node (ref "R301") (pin "1") (pinfunction "1_1") (pintype "passive"))
      (node (ref "X1") (pin "3") (pinfunction "Y_3") (pintype "input"))
    )
    (net (code "56") (name "RF-OUT") (class "Default")
      (node (ref "R326") (pin "2") (pinfunction "2_2") (pintype "passive"))
    )
    (net (code "57") (name "VCC2") (class "Default")
      (node (ref "C301") (pin "+") (pinfunction "+_+") (pintype "passive"))
      (node (ref "C304") (pin "1") (pinfunction "1_1") (pintype "passive"))
      (node (ref "C319") (pin "1") (pinfunction "1_1") (pintype "passive"))
      (node (ref "IC3") (pin "14") (pinfunction "P$14_14") (pintype "power_in"))
      (node (ref "IC3") (pin "16") (pinfunction "P$16_16") (pintype "power_in"))
      (node (ref "L301") (pin "2") (pinfunction "2_2") (pintype "passive"))
      (node (ref "R311") (pin "2") (pinfunction "2_2") (pintype "passive"))
      (node (ref "R313") (pin "1") (pinfunction "1_1") (pintype "passive"))
      (node (ref "R322") (pin "2") (pinfunction "2_2") (pintype "passive"))
      (node (ref "R330") (pin "2") (pinfunction "2_2") (pintype "passive"))
      (node (ref "R336") (pin "2") (pinfunction "2_2") (pintype "passive"))
      (node (ref "R338") (pin "1") (pinfunction "1_1") (pintype "passive"))
      (node (ref "T305") (pin "C") (pinfunction "C_C") (pintype "passive"))
    )
    (net (code "58") (name "VIDEO") (class "Default")
      (node (ref "C326") (pin "-") (pinfunction "-_-") (pintype "passive"))
    )
    (net (code "59") (name "unconnected-(CI301A-~{Q}-Pad2)") (class "Default")
      (node (ref "CI301") (pin "2") (pinfunction "~{Q}_2") (pintype "output"))
    )
    (net (code "60") (name "unconnected-(IC3-P$17-Pad17)") (class "Default")
      (node (ref "IC3") (pin "17") (pinfunction "P$17_17") (pintype "output"))
    )
    (net (code "61") (name "unconnected-(R321-PadE)") (class "Default")
      (node (ref "R321") (pin "E") (pinfunction "E_E") (pintype "passive"))
    )
  )
)
